# Pure_VCA.net
KiCad netlist of a schematic drawn in EAGLE
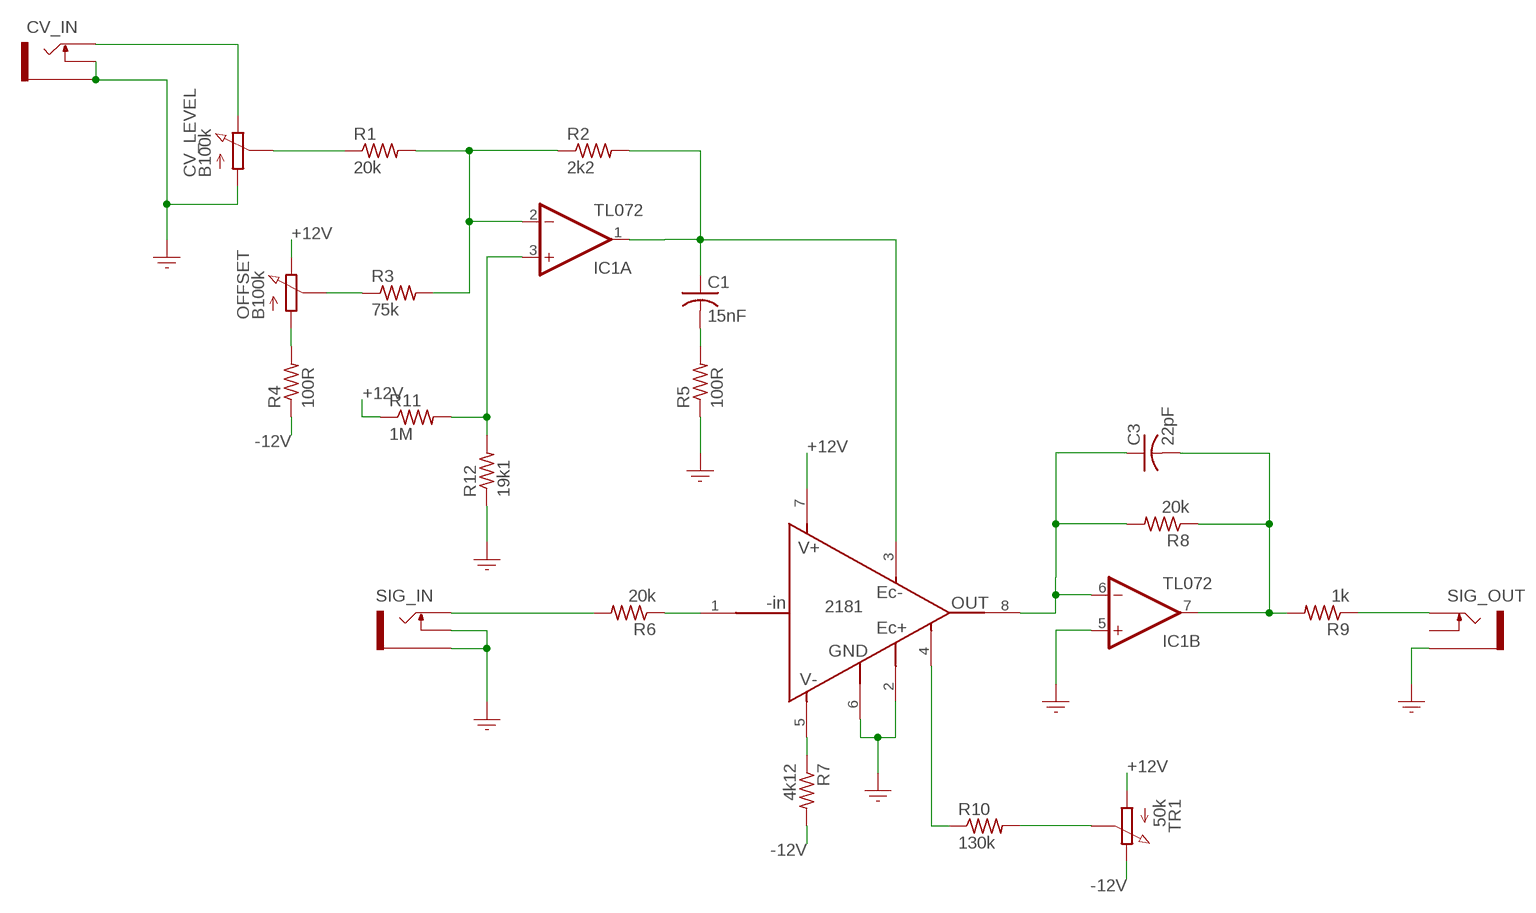
[diagram p0: schematic, sheet 1]
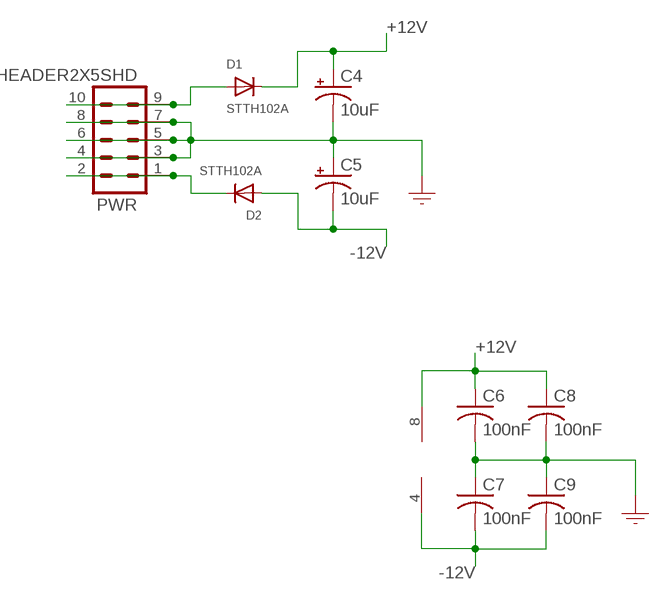
[diagram p1: schematic, sheet 2]

(export (version "E")
  (design (tool "Eeschema 10.0.6"))
  (components
    (comp (ref "C4")
      (value "10uF")
      (footprint "eagle-import:153CLV-0505")
      (libsource (lib "eagle-import") (part "CAPACITOR_POL-US153CLV-0505"))
    )
    (comp (ref "C5")
      (value "10uF")
      (footprint "eagle-import:153CLV-0505")
      (libsource (lib "eagle-import") (part "CAPACITOR_POL-US153CLV-0505"))
    )
    (comp (ref "C6")
      (value "100nF")
      (footprint "eagle-import:C0805")
      (libsource (lib "eagle-import") (part "CAPACITOR-USC0805"))
    )
    (comp (ref "C7")
      (value "100nF")
      (footprint "eagle-import:C0805")
      (libsource (lib "eagle-import") (part "CAPACITOR-USC0805"))
    )
    (comp (ref "C8")
      (value "100nF")
      (footprint "eagle-import:C0805")
      (libsource (lib "eagle-import") (part "CAPACITOR-USC0805"))
    )
    (comp (ref "C9")
      (value "100nF")
      (footprint "eagle-import:C0805")
      (libsource (lib "eagle-import") (part "CAPACITOR-USC0805"))
    )
    (comp (ref "D1")
      (value "STTH102A")
      (footprint "eagle-import:SMADIODE")
      (libsource (lib "eagle-import") (part "DIODESMA"))
    )
    (comp (ref "D2")
      (value "STTH102A")
      (footprint "eagle-import:SMADIODE")
      (libsource (lib "eagle-import") (part "DIODESMA"))
    )
    (comp (ref "IC1")
      (value "TL072")
      (footprint "eagle-import:SO08")
      (libsource (lib "eagle-import") (part "OPAMP_DUALD"))
    )
    (comp (ref "PWR")
      (value "HEADER2X5SHD")
      (footprint "eagle-import:2X5-SHROUDED")
      (libsource (lib "eagle-import") (part "HEADER2X5SHD"))
    )
    (comp (ref "C1")
      (value "15nF")
      (footprint "eagle-import:C0805")
      (libsource (lib "eagle-import") (part "CAPACITOR-USC0805"))
    )
    (comp (ref "C3")
      (value "22pF")
      (footprint "eagle-import:C0805")
      (libsource (lib "eagle-import") (part "CAPACITOR-USC0805"))
    )
    (comp (ref "CV_IN")
      (value "PJ301M-12")
      (footprint "eagle-import:PJ301M-12")
      (libsource (lib "eagle-import") (part "SOCKET_MONO_3.5MMPJ301M-12"))
    )
    (comp (ref "CV_LEVEL")
      (value "B100k")
      (footprint "eagle-import:POT_9MM_GREEN_KNOB")
      (libsource (lib "eagle-import") (part "RESISTOR_VARIABLEPOT_9MM_GREEN_KNOB"))
    )
    (comp (ref "IC2")
      (value "THAT2181")
      (footprint "eagle-import:SOIC--8")
      (libsource (lib "eagle-import") (part "VCA_THAT2181"))
    )
    (comp (ref "OFFSET")
      (value "B100k")
      (footprint "eagle-import:POT_9MM_BLUE_KNOB")
      (libsource (lib "eagle-import") (part "RESISTOR_VARIABLEPOT_9MM_BLUE_KNOB"))
    )
    (comp (ref "R1")
      (value "20k")
      (footprint "eagle-import:R0805")
      (libsource (lib "eagle-import") (part "RESISTOR_USR0805"))
    )
    (comp (ref "R2")
      (value "2k2")
      (footprint "eagle-import:R0805")
      (libsource (lib "eagle-import") (part "RESISTOR_USR0805"))
    )
    (comp (ref "R3")
      (value "75k")
      (footprint "eagle-import:R0805")
      (libsource (lib "eagle-import") (part "RESISTOR_USR0805"))
    )
    (comp (ref "R4")
      (value "100R")
      (footprint "eagle-import:R0805")
      (libsource (lib "eagle-import") (part "RESISTOR_USR0805"))
    )
    (comp (ref "R5")
      (value "100R")
      (footprint "eagle-import:R0805")
      (libsource (lib "eagle-import") (part "RESISTOR_USR0805"))
    )
    (comp (ref "R6")
      (value "20k")
      (footprint "eagle-import:R0805")
      (libsource (lib "eagle-import") (part "RESISTOR_USR0805"))
    )
    (comp (ref "R7")
      (value "4k12")
      (footprint "eagle-import:R0805")
      (libsource (lib "eagle-import") (part "RESISTOR_USR0805"))
    )
    (comp (ref "R8")
      (value "20k")
      (footprint "eagle-import:R0805")
      (libsource (lib "eagle-import") (part "RESISTOR_USR0805"))
    )
    (comp (ref "R9")
      (value "1k")
      (footprint "eagle-import:R0805")
      (libsource (lib "eagle-import") (part "RESISTOR_USR0805"))
    )
    (comp (ref "R10")
      (value "130k")
      (footprint "eagle-import:R0805")
      (libsource (lib "eagle-import") (part "RESISTOR_USR0805"))
    )
    (comp (ref "R11")
      (value "1M")
      (footprint "eagle-import:R0805")
      (libsource (lib "eagle-import") (part "RESISTOR_USR0805"))
    )
    (comp (ref "R12")
      (value "19k1")
      (footprint "eagle-import:R0805")
      (libsource (lib "eagle-import") (part "RESISTOR_USR0805"))
    )
    (comp (ref "SIG_IN")
      (value "PJ301M-12")
      (footprint "eagle-import:PJ301M-12")
      (libsource (lib "eagle-import") (part "SOCKET_MONO_3.5MMPJ301M-12"))
    )
    (comp (ref "SIG_OUT")
      (value "PJ301M-12")
      (footprint "eagle-import:PJ301M-12")
      (libsource (lib "eagle-import") (part "SOCKET_MONO_3.5MMPJ301M-12"))
    )
    (comp (ref "TR1")
      (value "50k")
      (footprint "eagle-import:TRIMMER_TH")
      (libsource (lib "eagle-import") (part "RESISTOR_VARIABLETRIMMER_TH"))
    )
  )
  (nets
    (net (code "1") (name "+12V") (class "Default")
      (node (ref "C4") (pin "+") (pinfunction "+_+") (pintype "passive"))
      (node (ref "C6") (pin "1") (pinfunction "1_1") (pintype "passive"))
      (node (ref "C8") (pin "1") (pinfunction "1_1") (pintype "passive"))
      (node (ref "D1") (pin "C") (pinfunction "C_C") (pintype "passive"))
      (node (ref "IC1") (pin "8") (pinfunction "V+_8") (pintype "power_in"))
      (node (ref "IC2") (pin "7") (pinfunction "V+_7") (pintype "bidirectional"))
      (node (ref "OFFSET") (pin "P$3") (pinfunction "3_P$3") (pintype "passive"))
      (node (ref "R11") (pin "1") (pinfunction "1_1") (pintype "passive"))
      (node (ref "TR1") (pin "1") (pinfunction "1_1") (pintype "passive"))
    )
    (net (code "2") (name "-12V") (class "Default")
      (node (ref "C5") (pin "-") (pinfunction "-_-") (pintype "passive"))
      (node (ref "C7") (pin "2") (pinfunction "2_2") (pintype "passive"))
      (node (ref "C9") (pin "2") (pinfunction "2_2") (pintype "passive"))
      (node (ref "D2") (pin "A") (pinfunction "A_A") (pintype "passive"))
      (node (ref "IC1") (pin "4") (pinfunction "V-_4") (pintype "power_in"))
      (node (ref "R4") (pin "1") (pinfunction "1_1") (pintype "passive"))
      (node (ref "R7") (pin "2") (pinfunction "2_2") (pintype "passive"))
      (node (ref "TR1") (pin "3") (pinfunction "3_3") (pintype "passive"))
    )
    (net (code "3") (name "GND") (class "Default")
      (node (ref "C4") (pin "-") (pinfunction "-_-") (pintype "passive"))
      (node (ref "C5") (pin "+") (pinfunction "+_+") (pintype "passive"))
      (node (ref "C6") (pin "2") (pinfunction "2_2") (pintype "passive"))
      (node (ref "C7") (pin "1") (pinfunction "1_1") (pintype "passive"))
      (node (ref "C8") (pin "2") (pinfunction "2_2") (pintype "passive"))
      (node (ref "C9") (pin "1") (pinfunction "1_1") (pintype "passive"))
      (node (ref "CV_IN") (pin "GND") (pinfunction "SLEEVE_GND") (pintype "passive"))
      (node (ref "CV_IN") (pin "NORM") (pinfunction "SWITCH_NORM") (pintype "passive"))
      (node (ref "CV_LEVEL") (pin "P$1") (pinfunction "1_P$1") (pintype "passive"))
      (node (ref "IC1") (pin "5") (pinfunction "+IN_5") (pintype "input"))
      (node (ref "IC2") (pin "2") (pinfunction "EC+_2") (pintype "bidirectional"))
      (node (ref "IC2") (pin "6") (pinfunction "GND_6") (pintype "bidirectional"))
      (node (ref "PWR") (pin "3") (pinfunction "3_3") (pintype "passive"))
      (node (ref "PWR") (pin "4") (pinfunction "4_4") (pintype "passive"))
      (node (ref "PWR") (pin "5") (pinfunction "5_5") (pintype "passive"))
      (node (ref "PWR") (pin "6") (pinfunction "6_6") (pintype "passive"))
      (node (ref "PWR") (pin "7") (pinfunction "7_7") (pintype "passive"))
      (node (ref "PWR") (pin "8") (pinfunction "8_8") (pintype "passive"))
      (node (ref "R12") (pin "1") (pinfunction "1_1") (pintype "passive"))
      (node (ref "R5") (pin "1") (pinfunction "1_1") (pintype "passive"))
      (node (ref "SIG_IN") (pin "GND") (pinfunction "SLEEVE_GND") (pintype "passive"))
      (node (ref "SIG_IN") (pin "NORM") (pinfunction "SWITCH_NORM") (pintype "passive"))
      (node (ref "SIG_OUT") (pin "GND") (pinfunction "SLEEVE_GND") (pintype "passive"))
    )
    (net (code "4") (name "Net-(C1-Pad2)") (class "Default")
      (node (ref "C1") (pin "2") (pinfunction "2_2") (pintype "passive"))
      (node (ref "R5") (pin "2") (pinfunction "2_2") (pintype "passive"))
    )
    (net (code "5") (name "Net-(CV_LEVEL-2)") (class "Default")
      (node (ref "CV_LEVEL") (pin "P$2") (pinfunction "2_P$2") (pintype "passive"))
      (node (ref "R1") (pin "1") (pinfunction "1_1") (pintype "passive"))
    )
    (net (code "6") (name "Net-(CV_LEVEL-3)") (class "Default")
      (node (ref "CV_IN") (pin "TIP") (pinfunction "TIP_TIP") (pintype "passive"))
      (node (ref "CV_LEVEL") (pin "P$3") (pinfunction "3_P$3") (pintype "passive"))
    )
    (net (code "7") (name "Net-(D1-PadA)") (class "Default")
      (node (ref "D1") (pin "A") (pinfunction "A_A") (pintype "passive"))
      (node (ref "PWR") (pin "10") (pinfunction "10_10") (pintype "passive"))
      (node (ref "PWR") (pin "9") (pinfunction "9_9") (pintype "passive"))
    )
    (net (code "8") (name "Net-(D2-PadC)") (class "Default")
      (node (ref "D2") (pin "C") (pinfunction "C_C") (pintype "passive"))
      (node (ref "PWR") (pin "1") (pinfunction "1_1") (pintype "passive"))
      (node (ref "PWR") (pin "2") (pinfunction "2_2") (pintype "passive"))
    )
    (net (code "9") (name "Net-(IC1A-+IN)") (class "Default")
      (node (ref "IC1") (pin "3") (pinfunction "+IN_3") (pintype "input"))
      (node (ref "R11") (pin "2") (pinfunction "2_2") (pintype "passive"))
      (node (ref "R12") (pin "2") (pinfunction "2_2") (pintype "passive"))
    )
    (net (code "10") (name "Net-(IC1A--IN)") (class "Default")
      (node (ref "IC1") (pin "2") (pinfunction "-IN_2") (pintype "input"))
      (node (ref "R1") (pin "2") (pinfunction "2_2") (pintype "passive"))
      (node (ref "R2") (pin "1") (pinfunction "1_1") (pintype "passive"))
      (node (ref "R3") (pin "2") (pinfunction "2_2") (pintype "passive"))
    )
    (net (code "11") (name "Net-(IC1A-OUT)") (class "Default")
      (node (ref "C1") (pin "1") (pinfunction "1_1") (pintype "passive"))
      (node (ref "IC1") (pin "1") (pinfunction "OUT_1") (pintype "output"))
      (node (ref "IC2") (pin "3") (pinfunction "EC-_3") (pintype "bidirectional"))
      (node (ref "R2") (pin "2") (pinfunction "2_2") (pintype "passive"))
    )
    (net (code "12") (name "Net-(IC1B--IN)") (class "Default")
      (node (ref "C3") (pin "1") (pinfunction "1_1") (pintype "passive"))
      (node (ref "IC1") (pin "6") (pinfunction "-IN_6") (pintype "input"))
      (node (ref "IC2") (pin "8") (pinfunction "OUT_8") (pintype "bidirectional"))
      (node (ref "R8") (pin "2") (pinfunction "2_2") (pintype "passive"))
    )
    (net (code "13") (name "Net-(IC1B-OUT)") (class "Default")
      (node (ref "C3") (pin "2") (pinfunction "2_2") (pintype "passive"))
      (node (ref "IC1") (pin "7") (pinfunction "OUT_7") (pintype "output"))
      (node (ref "R8") (pin "1") (pinfunction "1_1") (pintype "passive"))
      (node (ref "R9") (pin "2") (pinfunction "2_2") (pintype "passive"))
    )
    (net (code "14") (name "Net-(IC2--IN)") (class "Default")
      (node (ref "IC2") (pin "1") (pinfunction "-IN_1") (pintype "bidirectional"))
      (node (ref "R6") (pin "1") (pinfunction "1_1") (pintype "passive"))
    )
    (net (code "15") (name "Net-(IC2-SYM)") (class "Default")
      (node (ref "IC2") (pin "4") (pinfunction "SYM_4") (pintype "bidirectional"))
      (node (ref "R10") (pin "1") (pinfunction "1_1") (pintype "passive"))
    )
    (net (code "16") (name "Net-(IC2-V-)") (class "Default")
      (node (ref "IC2") (pin "5") (pinfunction "V-_5") (pintype "bidirectional"))
      (node (ref "R7") (pin "1") (pinfunction "1_1") (pintype "passive"))
    )
    (net (code "17") (name "Net-(OFFSET-1)") (class "Default")
      (node (ref "OFFSET") (pin "P$1") (pinfunction "1_P$1") (pintype "passive"))
      (node (ref "R4") (pin "2") (pinfunction "2_2") (pintype "passive"))
    )
    (net (code "18") (name "Net-(OFFSET-2)") (class "Default")
      (node (ref "OFFSET") (pin "P$2") (pinfunction "2_P$2") (pintype "passive"))
      (node (ref "R3") (pin "1") (pinfunction "1_1") (pintype "passive"))
    )
    (net (code "19") (name "Net-(R6-Pad2)") (class "Default")
      (node (ref "R6") (pin "2") (pinfunction "2_2") (pintype "passive"))
      (node (ref "SIG_IN") (pin "TIP") (pinfunction "TIP_TIP") (pintype "passive"))
    )
    (net (code "20") (name "Net-(R9-Pad1)") (class "Default")
      (node (ref "R9") (pin "1") (pinfunction "1_1") (pintype "passive"))
      (node (ref "SIG_OUT") (pin "TIP") (pinfunction "TIP_TIP") (pintype "passive"))
    )
    (net (code "21") (name "Net-(R10-Pad2)") (class "Default")
      (node (ref "R10") (pin "2") (pinfunction "2_2") (pintype "passive"))
      (node (ref "TR1") (pin "2") (pinfunction "2_2") (pintype "passive"))
    )
    (net (code "22") (name "unconnected-(SIG_OUT-SWITCH-PadNORM)") (class "Default")
      (node (ref "SIG_OUT") (pin "NORM") (pinfunction "SWITCH_NORM") (pintype "passive"))
    )
  )
)
